# Analog_Inputs.net
KiCad netlist of a schematic drawn in Altium Designer
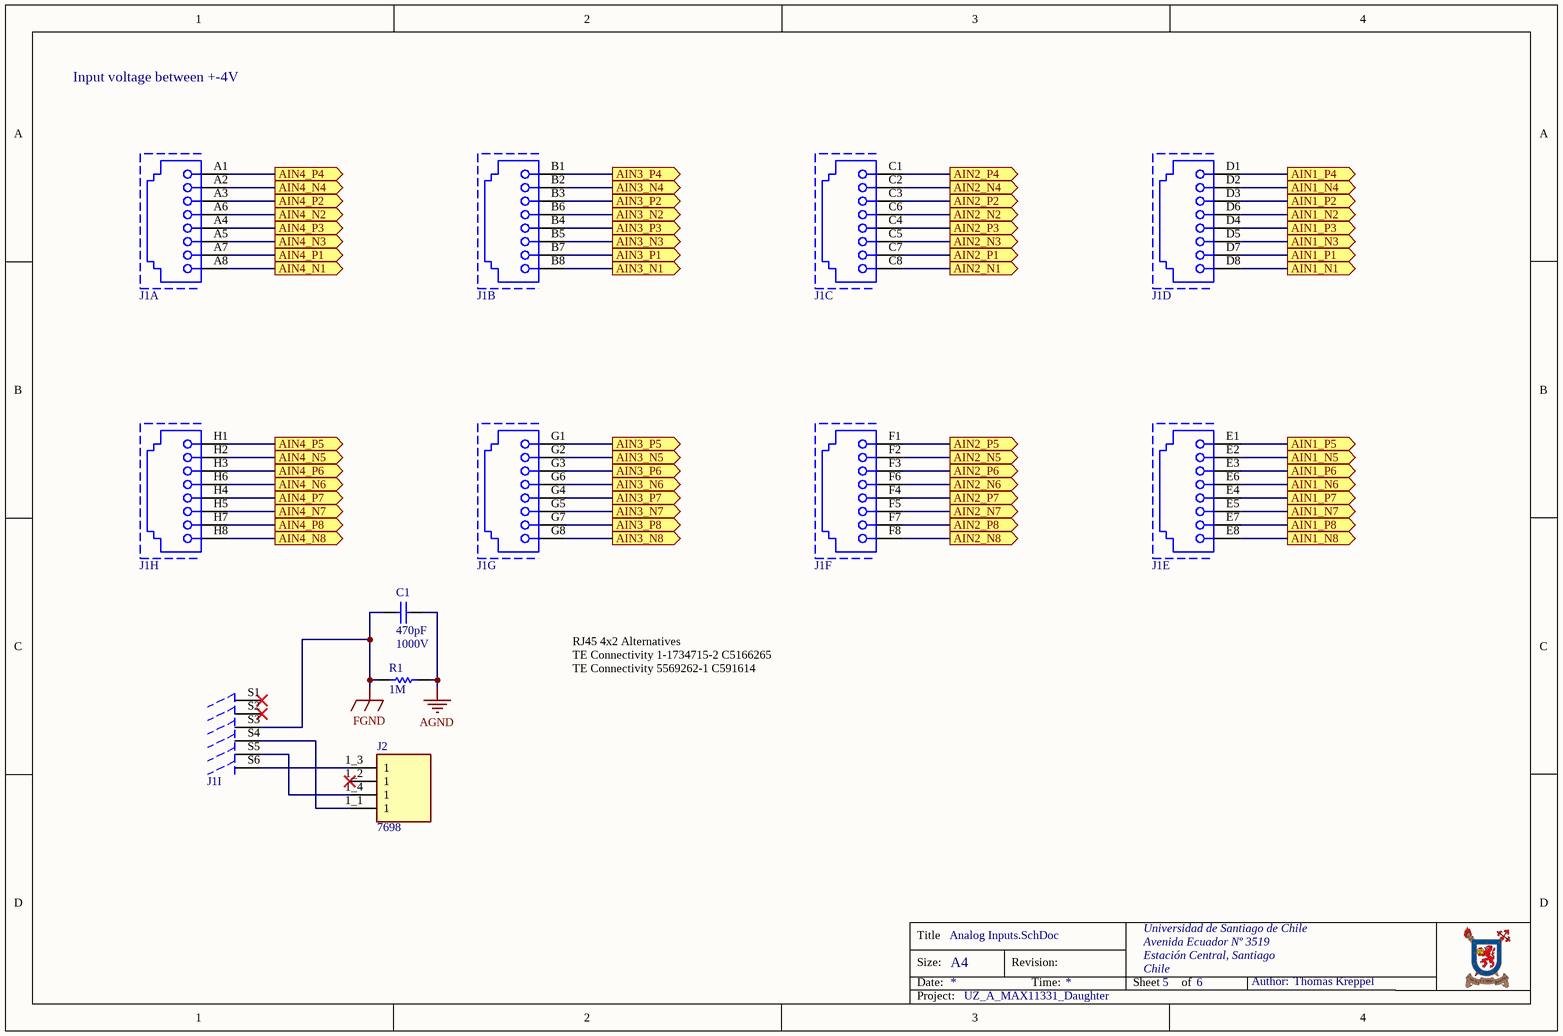
[diagram p0: Analog Inputs.SchDoc]

(export (version "E")
  (design (tool "Eeschema 10.0.6"))
  (components
    (comp (ref "C1")
      (value "470pF")
      (footprint "RES_1206")
      (description "Capacitor")
      (fields
        (field (name "MPN") "885342208017")
        (field (name "VOLTAGE") "1000V")
        (field (name "MF") "Würth Elektronik")
      )
      (libsource (lib "Componentes_SOC") (part "Cap_1206"))
    )
    (comp (ref "J1")
      (value "Conector RJ-45 4x2")
      (footprint "RJ45 - 4x2")
      (fields
        (field (name "MPN") "5569262-1")
        (field (name "MF") "TE Connectivity")
        (field (name "LCSC PART NUMBER") "C591614")
      )
      (libsource (lib "Componentes_SOC") (part "Conector RJ-45 4x2"))
    )
    (comp (ref "J2")
      (value "7698")
      (footprint "KEYSTONE_7698")
      (description "Screw Terminal;Nickel;15 Amp;Snap-In;Vertical;Unassembled;M3 Thrd ¦ Keystone Electronics 7698")
      (fields (field (name "MF") "Keystone") (field (name "LCSC PART NUMBER") "C6708741"))
      (libsource (lib "Componentes_SOC") (part "7698"))
    )
    (comp (ref "R1")
      (value "1M")
      (footprint "RES_1206")
      (description "Resistor")
      (fields (field (name "MPN") "RC1206FR-071ML") (field (name "MF") "Yageo"))
      (libsource (lib "Componentes_SOC") (part "Res1206"))
    )
  )
  (nets
    (net (code "1") (name "/AIN1_N1") (class "Default")
      (node (ref "J1") (pin "D8") (pinfunction "D8_D8") (pintype "passive"))
    )
    (net (code "2") (name "/AIN1_N2") (class "Default")
      (node (ref "J1") (pin "D6") (pinfunction "D6_D6") (pintype "passive"))
    )
    (net (code "3") (name "/AIN1_N3") (class "Default")
      (node (ref "J1") (pin "D5") (pinfunction "D5_D5") (pintype "passive"))
    )
    (net (code "4") (name "/AIN1_N4") (class "Default")
      (node (ref "J1") (pin "D2") (pinfunction "D2_D2") (pintype "passive"))
    )
    (net (code "5") (name "/AIN1_N5") (class "Default")
      (node (ref "J1") (pin "E2") (pinfunction "E2_E2") (pintype "passive"))
    )
    (net (code "6") (name "/AIN1_N6") (class "Default")
      (node (ref "J1") (pin "E6") (pinfunction "E6_E6") (pintype "passive"))
    )
    (net (code "7") (name "/AIN1_N7") (class "Default")
      (node (ref "J1") (pin "E5") (pinfunction "E5_E5") (pintype "passive"))
    )
    (net (code "8") (name "/AIN1_N8") (class "Default")
      (node (ref "J1") (pin "E8") (pinfunction "E8_E8") (pintype "passive"))
    )
    (net (code "9") (name "/AIN1_P1") (class "Default")
      (node (ref "J1") (pin "D7") (pinfunction "D7_D7") (pintype "passive"))
    )
    (net (code "10") (name "/AIN1_P2") (class "Default")
      (node (ref "J1") (pin "D3") (pinfunction "D3_D3") (pintype "passive"))
    )
    (net (code "11") (name "/AIN1_P3") (class "Default")
      (node (ref "J1") (pin "D4") (pinfunction "D4_D4") (pintype "passive"))
    )
    (net (code "12") (name "/AIN1_P4") (class "Default")
      (node (ref "J1") (pin "D1") (pinfunction "D1_D1") (pintype "passive"))
    )
    (net (code "13") (name "/AIN1_P5") (class "Default")
      (node (ref "J1") (pin "E1") (pinfunction "E1_E1") (pintype "passive"))
    )
    (net (code "14") (name "/AIN1_P6") (class "Default")
      (node (ref "J1") (pin "E3") (pinfunction "E3_E3") (pintype "passive"))
    )
    (net (code "15") (name "/AIN1_P7") (class "Default")
      (node (ref "J1") (pin "E4") (pinfunction "E4_E4") (pintype "passive"))
    )
    (net (code "16") (name "/AIN1_P8") (class "Default")
      (node (ref "J1") (pin "E7") (pinfunction "E7_E7") (pintype "passive"))
    )
    (net (code "17") (name "/AIN2_N1") (class "Default")
      (node (ref "J1") (pin "C8") (pinfunction "C8_C8") (pintype "passive"))
    )
    (net (code "18") (name "/AIN2_N2") (class "Default")
      (node (ref "J1") (pin "C6") (pinfunction "C6_C6") (pintype "passive"))
    )
    (net (code "19") (name "/AIN2_N3") (class "Default")
      (node (ref "J1") (pin "C5") (pinfunction "C5_C5") (pintype "passive"))
    )
    (net (code "20") (name "/AIN2_N4") (class "Default")
      (node (ref "J1") (pin "C2") (pinfunction "C2_C2") (pintype "passive"))
    )
    (net (code "21") (name "/AIN2_N5") (class "Default")
      (node (ref "J1") (pin "F2") (pinfunction "F2_F2") (pintype "passive"))
    )
    (net (code "22") (name "/AIN2_N6") (class "Default")
      (node (ref "J1") (pin "F6") (pinfunction "F6_F6") (pintype "passive"))
    )
    (net (code "23") (name "/AIN2_N7") (class "Default")
      (node (ref "J1") (pin "F5") (pinfunction "F5_F5") (pintype "passive"))
    )
    (net (code "24") (name "/AIN2_N8") (class "Default")
      (node (ref "J1") (pin "F8") (pinfunction "F8_F8") (pintype "passive"))
    )
    (net (code "25") (name "/AIN2_P1") (class "Default")
      (node (ref "J1") (pin "C7") (pinfunction "C7_C7") (pintype "passive"))
    )
    (net (code "26") (name "/AIN2_P2") (class "Default")
      (node (ref "J1") (pin "C3") (pinfunction "C3_C3") (pintype "passive"))
    )
    (net (code "27") (name "/AIN2_P3") (class "Default")
      (node (ref "J1") (pin "C4") (pinfunction "C4_C4") (pintype "passive"))
    )
    (net (code "28") (name "/AIN2_P4") (class "Default")
      (node (ref "J1") (pin "C1") (pinfunction "C1_C1") (pintype "passive"))
    )
    (net (code "29") (name "/AIN2_P5") (class "Default")
      (node (ref "J1") (pin "F1") (pinfunction "F1_F1") (pintype "passive"))
    )
    (net (code "30") (name "/AIN2_P6") (class "Default")
      (node (ref "J1") (pin "F3") (pinfunction "F3_F3") (pintype "passive"))
    )
    (net (code "31") (name "/AIN2_P7") (class "Default")
      (node (ref "J1") (pin "F4") (pinfunction "F4_F4") (pintype "passive"))
    )
    (net (code "32") (name "/AIN2_P8") (class "Default")
      (node (ref "J1") (pin "F7") (pinfunction "F7_F7") (pintype "passive"))
    )
    (net (code "33") (name "/AIN3_N1") (class "Default")
      (node (ref "J1") (pin "B8") (pinfunction "B8_B8") (pintype "passive"))
    )
    (net (code "34") (name "/AIN3_N2") (class "Default")
      (node (ref "J1") (pin "B6") (pinfunction "B6_B6") (pintype "passive"))
    )
    (net (code "35") (name "/AIN3_N3") (class "Default")
      (node (ref "J1") (pin "B5") (pinfunction "B5_B5") (pintype "passive"))
    )
    (net (code "36") (name "/AIN3_N4") (class "Default")
      (node (ref "J1") (pin "B2") (pinfunction "B2_B2") (pintype "passive"))
    )
    (net (code "37") (name "/AIN3_N5") (class "Default")
      (node (ref "J1") (pin "G2") (pinfunction "G2_G2") (pintype "passive"))
    )
    (net (code "38") (name "/AIN3_N6") (class "Default")
      (node (ref "J1") (pin "G6") (pinfunction "G6_G6") (pintype "passive"))
    )
    (net (code "39") (name "/AIN3_N7") (class "Default")
      (node (ref "J1") (pin "G5") (pinfunction "G5_G5") (pintype "passive"))
    )
    (net (code "40") (name "/AIN3_N8") (class "Default")
      (node (ref "J1") (pin "G8") (pinfunction "G8_G8") (pintype "passive"))
    )
    (net (code "41") (name "/AIN3_P1") (class "Default")
      (node (ref "J1") (pin "B7") (pinfunction "B7_B7") (pintype "passive"))
    )
    (net (code "42") (name "/AIN3_P2") (class "Default")
      (node (ref "J1") (pin "B3") (pinfunction "B3_B3") (pintype "passive"))
    )
    (net (code "43") (name "/AIN3_P3") (class "Default")
      (node (ref "J1") (pin "B4") (pinfunction "B4_B4") (pintype "passive"))
    )
    (net (code "44") (name "/AIN3_P4") (class "Default")
      (node (ref "J1") (pin "B1") (pinfunction "B1_B1") (pintype "passive"))
    )
    (net (code "45") (name "/AIN3_P5") (class "Default")
      (node (ref "J1") (pin "G1") (pinfunction "G1_G1") (pintype "passive"))
    )
    (net (code "46") (name "/AIN3_P6") (class "Default")
      (node (ref "J1") (pin "G3") (pinfunction "G3_G3") (pintype "passive"))
    )
    (net (code "47") (name "/AIN3_P7") (class "Default")
      (node (ref "J1") (pin "G4") (pinfunction "G4_G4") (pintype "passive"))
    )
    (net (code "48") (name "/AIN3_P8") (class "Default")
      (node (ref "J1") (pin "G7") (pinfunction "G7_G7") (pintype "passive"))
    )
    (net (code "49") (name "/AIN4_N1") (class "Default")
      (node (ref "J1") (pin "A8") (pinfunction "A8_A8") (pintype "passive"))
    )
    (net (code "50") (name "/AIN4_N2") (class "Default")
      (node (ref "J1") (pin "A6") (pinfunction "A6_A6") (pintype "passive"))
    )
    (net (code "51") (name "/AIN4_N3") (class "Default")
      (node (ref "J1") (pin "A5") (pinfunction "A5_A5") (pintype "passive"))
    )
    (net (code "52") (name "/AIN4_N4") (class "Default")
      (node (ref "J1") (pin "A2") (pinfunction "A2_A2") (pintype "passive"))
    )
    (net (code "53") (name "/AIN4_N5") (class "Default")
      (node (ref "J1") (pin "H2") (pinfunction "H2_H2") (pintype "passive"))
    )
    (net (code "54") (name "/AIN4_N6") (class "Default")
      (node (ref "J1") (pin "H6") (pinfunction "H6_H6") (pintype "passive"))
    )
    (net (code "55") (name "/AIN4_N7") (class "Default")
      (node (ref "J1") (pin "H5") (pinfunction "H5_H5") (pintype "passive"))
    )
    (net (code "56") (name "/AIN4_N8") (class "Default")
      (node (ref "J1") (pin "H8") (pinfunction "H8_H8") (pintype "passive"))
    )
    (net (code "57") (name "/AIN4_P1") (class "Default")
      (node (ref "J1") (pin "A7") (pinfunction "A7_A7") (pintype "passive"))
    )
    (net (code "58") (name "/AIN4_P2") (class "Default")
      (node (ref "J1") (pin "A3") (pinfunction "A3_A3") (pintype "passive"))
    )
    (net (code "59") (name "/AIN4_P3") (class "Default")
      (node (ref "J1") (pin "A4") (pinfunction "A4_A4") (pintype "passive"))
    )
    (net (code "60") (name "/AIN4_P4") (class "Default")
      (node (ref "J1") (pin "A1") (pinfunction "A1_A1") (pintype "passive"))
    )
    (net (code "61") (name "/AIN4_P5") (class "Default")
      (node (ref "J1") (pin "H1") (pinfunction "H1_H1") (pintype "passive"))
    )
    (net (code "62") (name "/AIN4_P6") (class "Default")
      (node (ref "J1") (pin "H3") (pinfunction "H3_H3") (pintype "passive"))
    )
    (net (code "63") (name "/AIN4_P7") (class "Default")
      (node (ref "J1") (pin "H4") (pinfunction "H4_H4") (pintype "passive"))
    )
    (net (code "64") (name "/AIN4_P8") (class "Default")
      (node (ref "J1") (pin "H7") (pinfunction "H7_H7") (pintype "passive"))
    )
    (net (code "65") (name "AGND") (class "Default")
      (node (ref "C1") (pin "2") (pinfunction "2_2") (pintype "passive"))
      (node (ref "R1") (pin "2") (pinfunction "2_2") (pintype "passive"))
    )
    (net (code "66") (name "FGND") (class "Default")
      (node (ref "C1") (pin "1") (pinfunction "1_1") (pintype "passive"))
      (node (ref "J1") (pin "S3") (pinfunction "S3_S3") (pintype "passive"))
      (node (ref "R1") (pin "1") (pinfunction "1_1") (pintype "passive"))
    )
    (net (code "67") (name "Net-(J1-PadS4)") (class "Default")
      (node (ref "J1") (pin "S4") (pinfunction "S4_S4") (pintype "passive"))
      (node (ref "J2") (pin "1_1") (pinfunction "1_1_1") (pintype "passive"))
    )
    (net (code "68") (name "Net-(J1-PadS5)") (class "Default")
      (node (ref "J1") (pin "S5") (pinfunction "S5_S5") (pintype "passive"))
      (node (ref "J2") (pin "1_4") (pinfunction "1_1_4") (pintype "passive"))
    )
    (net (code "69") (name "Net-(J1-PadS6)") (class "Default")
      (node (ref "J1") (pin "S6") (pinfunction "S6_S6") (pintype "passive"))
      (node (ref "J2") (pin "1_3") (pinfunction "1_1_3") (pintype "passive"))
    )
    (net (code "70") (name "unconnected-(J1-PadS1)") (class "Default")
      (node (ref "J1") (pin "S1") (pinfunction "S1_S1") (pintype "passive+no_connect"))
    )
    (net (code "71") (name "unconnected-(J1-PadS2)") (class "Default")
      (node (ref "J1") (pin "S2") (pinfunction "S2_S2") (pintype "passive+no_connect"))
    )
    (net (code "72") (name "unconnected-(J2-1-Pad1_2)") (class "Default")
      (node (ref "J2") (pin "1_2") (pinfunction "1_1_2") (pintype "passive+no_connect"))
    )
  )
)
